# Servo_control_module.net
KiCad netlist of a schematic drawn in Altium Designer
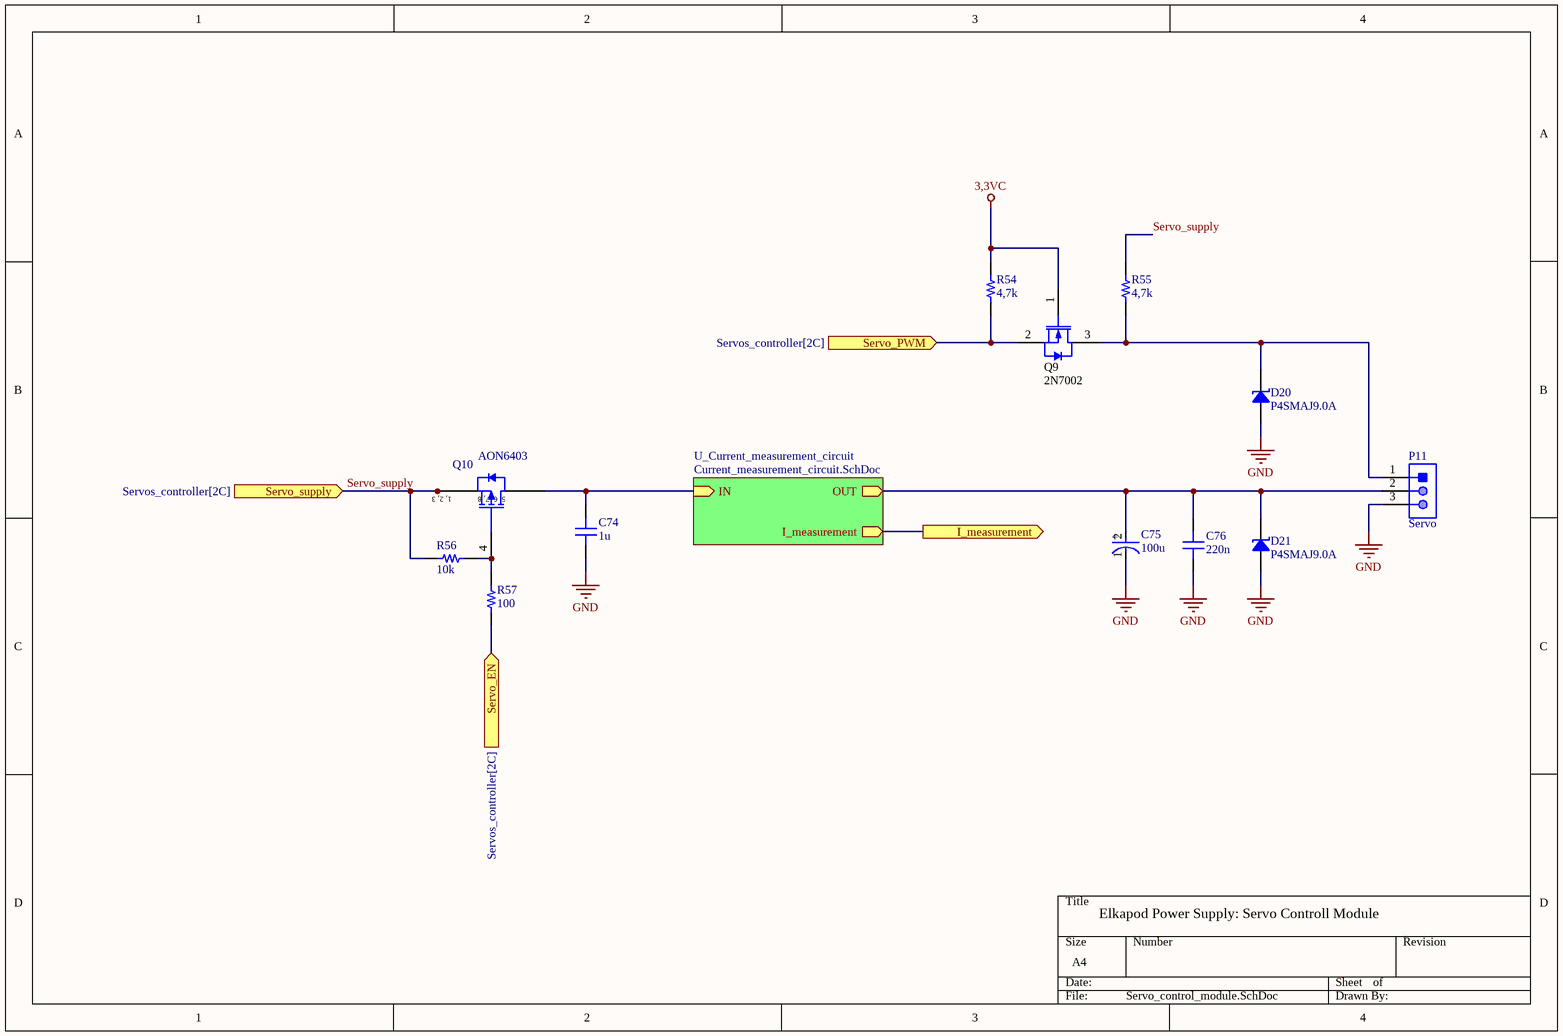
[diagram p0: Servo_control_module.SchDoc]

(export (version "E")
  (design (tool "Eeschema 10.0.6"))
  (components
    (comp (ref "C74")
      (value "1u")
      (footprint "CAP 0603_1608")
      (description "CAP CER 1uF 16V X5R 0603")
      (fields (field (name "PART NUMBER") "C0603C272F3GAC7867") (field (name "MANUFACTURER") "KEMET"))
      (libsource (lib "Celestial Altium Library - altium_library") (part "Capacitor"))
    )
    (comp (ref "C75")
      (value "100u")
      (footprint "FP-FKE-MFG")
      (description "CAP ALUM 100UF 20% 25V SMD")
      (fields (field (name "TOLERANCE") "20%") (field (name "VOLTAGE") "25V"))
      (libsource (lib "Altium Content Vault") (part "203bc49f2ac43e59fd269a8c329ed05"))
    )
    (comp (ref "C76")
      (value "220n")
      (footprint "CAP 0603_1608")
      (description "CAP CER 220nF 25V X5R 0603")
      (fields (field (name "PART NUMBER") "C0603C272F3GAC7867") (field (name "MANUFACTURER") "KEMET"))
      (libsource (lib "Celestial Altium Library - altium_library") (part "Capacitor"))
    )
    (comp (ref "D20")
      (value "P4SMAJ9.0A")
      (footprint "DO214AC SMA")
      (description "TVS DIODE 9VDC DO214AC")
      (libsource (lib "Celestial Altium Library - altium_library") (part "DIODE TVS UNI"))
    )
    (comp (ref "D21")
      (value "P4SMAJ9.0A")
      (footprint "DO214AC SMA")
      (description "TVS DIODE 9VDC DO214AC")
      (libsource (lib "Celestial Altium Library - altium_library") (part "DIODE TVS UNI"))
    )
    (comp (ref "P11")
      (value "Servo")
      (footprint "MOLX-22-23-2031_V")
      (description "Male Header, Pitch 2.54 mm, 1 x 3 Position, Height 8.18 mm, Tail Length 3.56 mm, RoHS, Bulk")
      (fields (field (name "MANUFACTURER") "Molex"))
      (libsource (lib "Altium Content Vault") (part "CN-1P-M-R3"))
    )
    (comp (ref "Q9")
      (value "2N7002")
      (footprint "INF-PG-SOT23_M")
      (fields (field (name "MANUFACTURER") "Infineon"))
      (libsource (lib "Altium Content Vault") (part "INF-NDMOS-GSD-3"))
    )
    (comp (ref "Q10")
      (value "AON6403")
      (footprint "DFN5x6")
      (description "P-MOSFET; 67A; 30V; DFN5x6")
      (libsource (lib "My_transistors") (part "AON6403"))
    )
    (comp (ref "R54")
      (value "4,7k")
      (footprint "RES 0603_1608")
      (description "RES 4,7K OHM 1% 0,1W 0603")
      (fields
        (field (name "PART NUMBER") "RNCS0603BKE10K0")
        (field (name "MANUFACTURER") "Stackpole Electronics Inc")
      )
      (libsource (lib "Celestial Altium Library - altium_library") (part "Resistor"))
    )
    (comp (ref "R55")
      (value "4,7k")
      (footprint "RES 0603_1608")
      (description "RES 4,7K OHM 1% 0,1W 0603")
      (fields
        (field (name "PART NUMBER") "RNCS0603BKE10K0")
        (field (name "MANUFACTURER") "Stackpole Electronics Inc")
      )
      (libsource (lib "Celestial Altium Library - altium_library") (part "Resistor"))
    )
    (comp (ref "R56")
      (value "10k")
      (footprint "RES 0603_1608")
      (description "RES 10K OHM 1% 0,1W 0603")
      (fields
        (field (name "PART NUMBER") "RNCS0603BKE10K0")
        (field (name "MANUFACTURER") "Stackpole Electronics Inc")
      )
      (libsource (lib "Celestial Altium Library - altium_library") (part "Resistor"))
    )
    (comp (ref "R57")
      (value "100")
      (footprint "RES 0603_1608")
      (description "RES 100 OHM 1% 0,1W 0603")
      (fields
        (field (name "PART NUMBER") "RNCS0603BKE10K0")
        (field (name "MANUFACTURER") "Stackpole Electronics Inc")
      )
      (libsource (lib "Celestial Altium Library - altium_library") (part "Resistor"))
    )
  )
  (nets
    (net (code "1") (name "/IN") (class "Default")
      (node (ref "C74") (pin "2") (pinfunction "2_2") (pintype "passive"))
      (node (ref "Q10") (pin "5-6-7-8") (pinfunction "D_5-6-7-8") (pintype "passive"))
    )
    (net (code "3") (name "/OUT") (class "Default")
      (node (ref "C75") (pin "2") (pinfunction "A_2") (pintype "passive"))
      (node (ref "C76") (pin "1") (pinfunction "1_1") (pintype "passive"))
      (node (ref "D21") (pin "2") (pinfunction "2_2") (pintype "passive"))
      (node (ref "P11") (pin "2") (pinfunction "2_2") (pintype "passive"))
    )
    (net (code "4") (name "/Servo_EN") (class "Default")
      (node (ref "R57") (pin "1") (pinfunction "1_1") (pintype "passive"))
    )
    (net (code "5") (name "/Servo_PWM") (class "Default")
      (node (ref "Q9") (pin "2") (pinfunction "SOURCE_2") (pintype "passive"))
      (node (ref "R54") (pin "1") (pinfunction "1_1") (pintype "passive"))
    )
    (net (code "6") (name "/Servo_supply") (class "Default")
      (node (ref "Q10") (pin "1") (pinfunction "S_1") (pintype "passive"))
      (node (ref "Q10") (pin "2") (pinfunction "S_2") (pintype "passive"))
      (node (ref "Q10") (pin "3") (pinfunction "S_3") (pintype "passive"))
      (node (ref "R55") (pin "2") (pinfunction "2_2") (pintype "passive"))
      (node (ref "R56") (pin "1") (pinfunction "1_1") (pintype "passive"))
    )
    (net (code "7") (name "3,3VC") (class "Default")
      (node (ref "Q9") (pin "1") (pinfunction "GATE_1") (pintype "passive"))
      (node (ref "R54") (pin "2") (pinfunction "2_2") (pintype "passive"))
    )
    (net (code "8") (name "GND") (class "Default")
      (node (ref "C74") (pin "1") (pinfunction "1_1") (pintype "passive"))
      (node (ref "C75") (pin "1") (pinfunction "C_1") (pintype "passive"))
      (node (ref "C76") (pin "2") (pinfunction "2_2") (pintype "passive"))
      (node (ref "D20") (pin "1") (pinfunction "1_1") (pintype "passive"))
      (node (ref "D21") (pin "1") (pinfunction "1_1") (pintype "passive"))
      (node (ref "P11") (pin "3") (pinfunction "3_3") (pintype "passive"))
    )
    (net (code "9") (name "Net-(Q9-DRAIN)") (class "Default")
      (node (ref "D20") (pin "2") (pinfunction "2_2") (pintype "passive"))
      (node (ref "P11") (pin "1") (pinfunction "1_1") (pintype "passive"))
      (node (ref "Q9") (pin "3") (pinfunction "DRAIN_3") (pintype "passive"))
      (node (ref "R55") (pin "1") (pinfunction "1_1") (pintype "passive"))
    )
    (net (code "10") (name "Net-(Q10-G)") (class "Default")
      (node (ref "Q10") (pin "4") (pinfunction "G_4") (pintype "passive"))
      (node (ref "R56") (pin "2") (pinfunction "2_2") (pintype "passive"))
      (node (ref "R57") (pin "2") (pinfunction "2_2") (pintype "passive"))
    )
  )
)
